# POWER_STAGE.net
KiCad netlist of a schematic drawn in Altium Designer
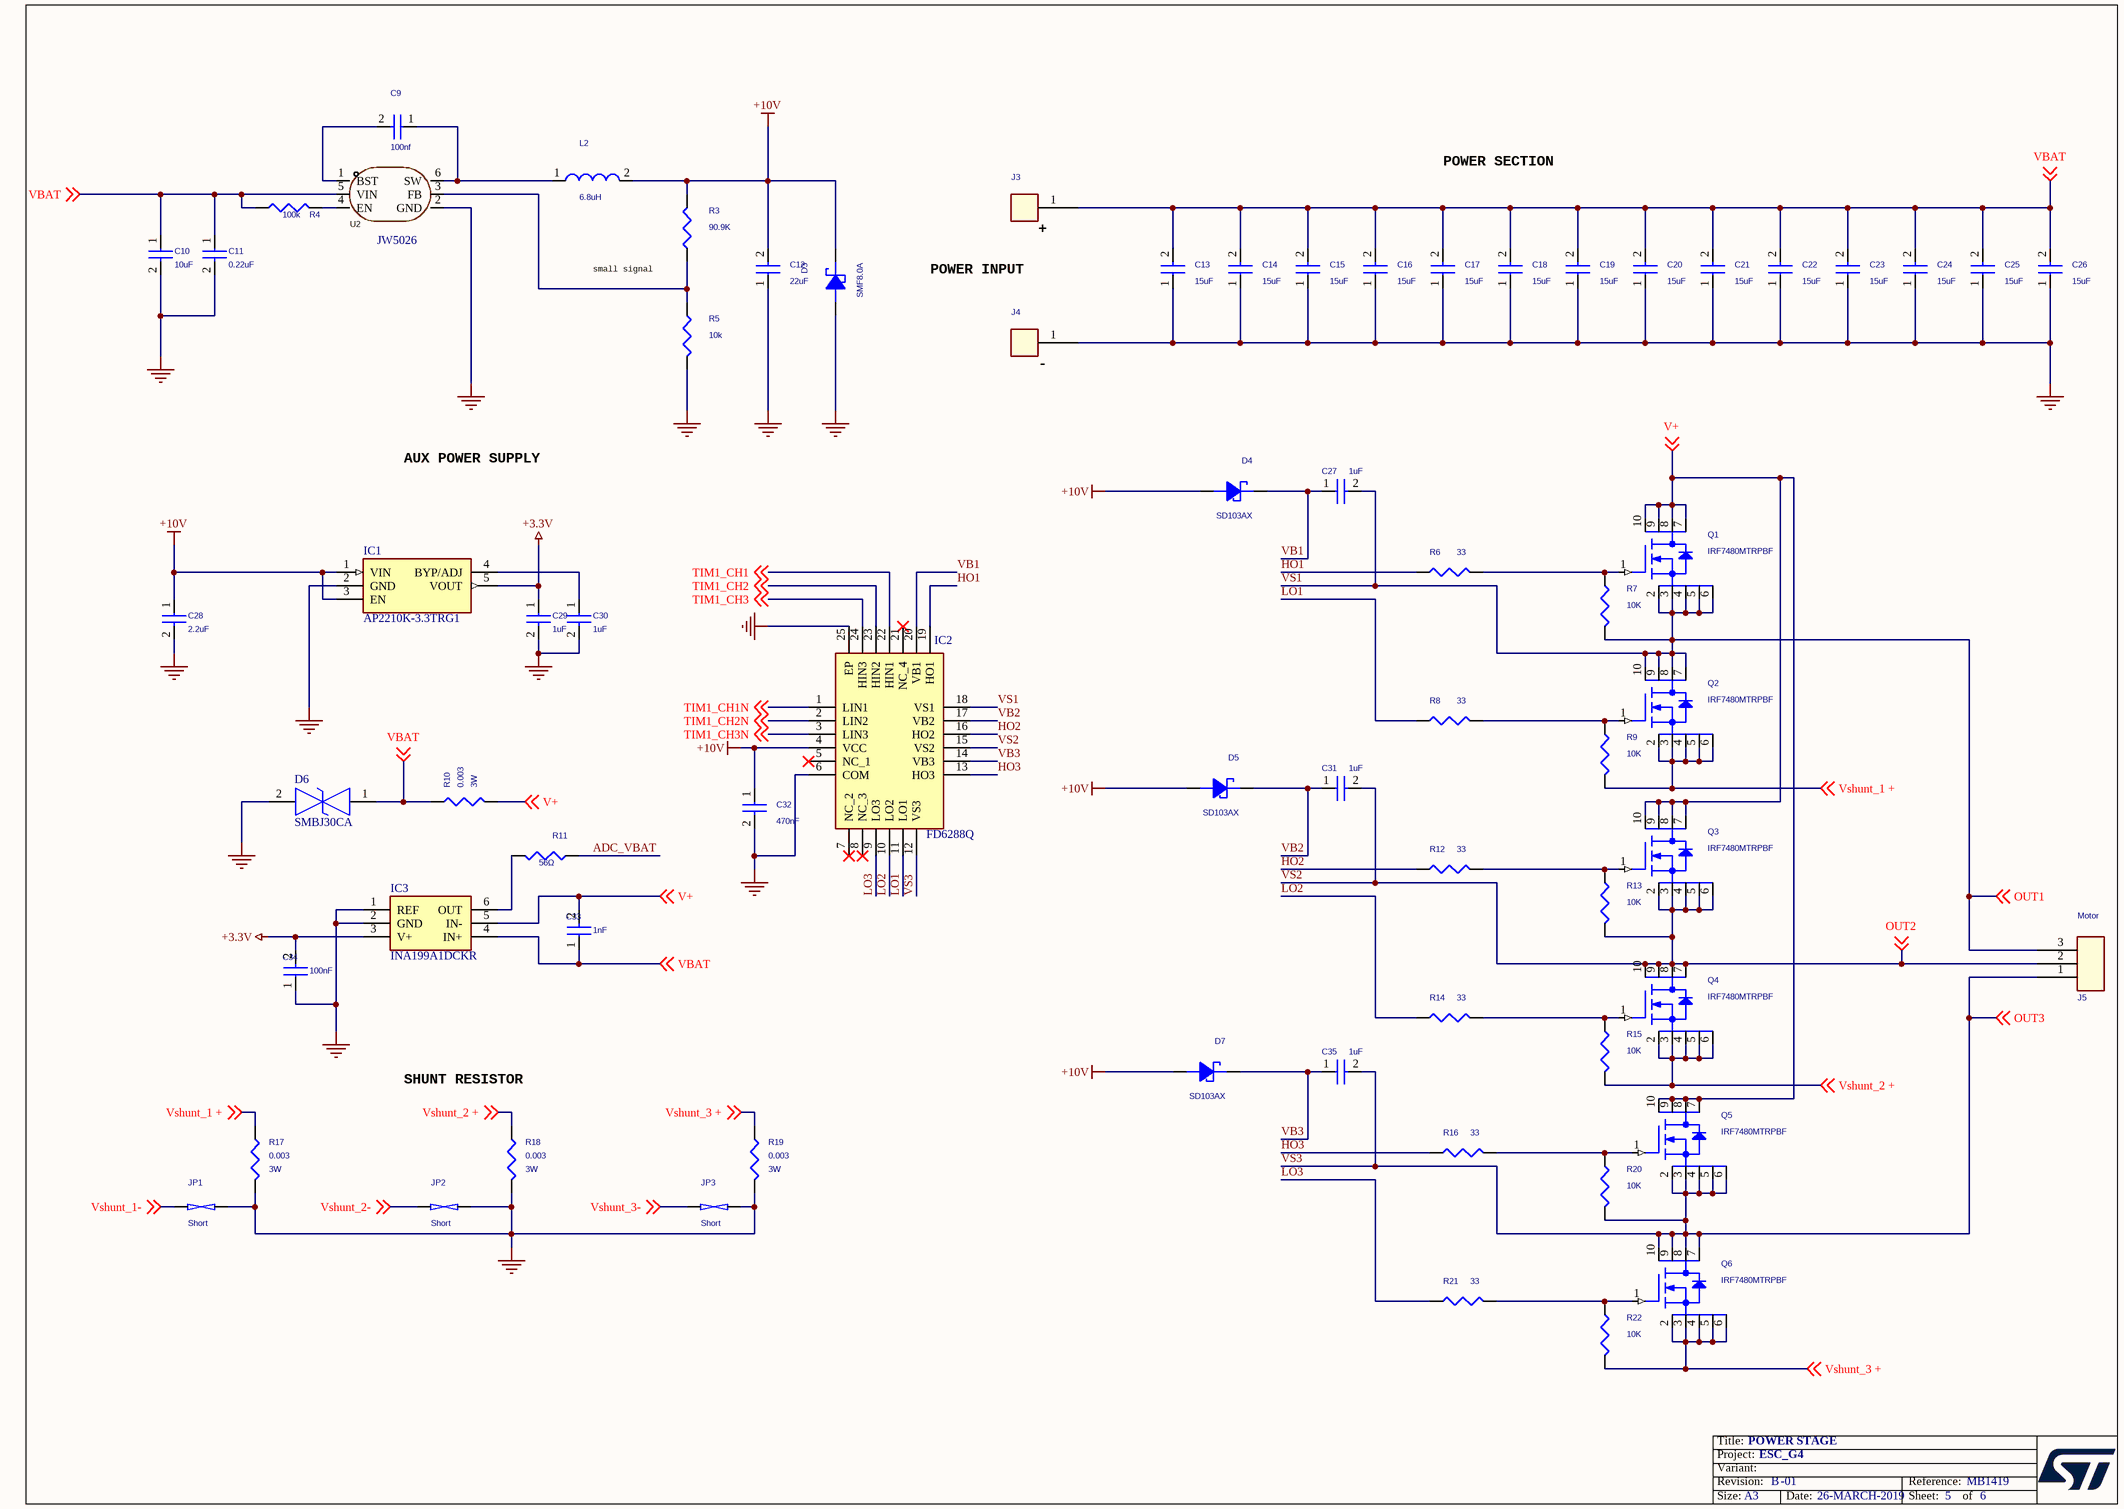
[diagram p0: POWER STAGE.SchDoc]

(export (version "E")
  (design (tool "Eeschema 10.0.6"))
  (components
    (comp (ref "C9")
      (value "100nf")
      (footprint "C_0402")
      (description "CAP CER 3900PF 16V X7R 0402")
      (fields (field (name "MANUFACTURER") "KEMET") (field (name "TOLERANCE") "10%"))
      (libsource (lib "*") (part "CAP_Dup1"))
    )
    (comp (ref "C10")
      (value "10uF")
      (footprint "C_1206")
      (description "CAP CER 10UF 50V X7R 1206")
      (fields
        (field (name "MANUFACTURER") "Samsung Electro-Mechanics America, Inc.")
        (field (name "TOLERANCE") "10%")
      )
      (libsource (lib "*") (part "CAP_Dup1"))
    )
    (comp (ref "C11")
      (value "0.22uF")
      (footprint "C_0603_HD")
      (description "CAP CER 0.22UF 50V X7R 0603")
      (fields (field (name "MANUFACTURER") "TDK Corporation") (field (name "TOLERANCE") "10%"))
      (libsource (lib "*") (part "CAP_Dup1"))
    )
    (comp (ref "C12")
      (value "22uF")
      (footprint "C_1206")
      (description "CAP CER 22UF 25V X5R 1206")
      (fields
        (field (name "MANUFACTURER") "Murata Electronics North America")
        (field (name "TOLERANCE") "20%")
      )
      (libsource (lib "*") (part "CAP_Dup1"))
    )
    (comp (ref "C13")
      (value "15uF")
      (footprint "C_0805_HD")
      (description "CAP CER 15UF 35V X5R 0805")
      (fields (field (name "PART_NUMBER") "TMP-773") (field (name "TOLERANCE") "20%"))
      (libsource (lib "*") (part "CAP_Dup1"))
    )
    (comp (ref "C14")
      (value "15uF")
      (footprint "C_0805_HD")
      (description "CAP CER 15UF 35V X5R 0805")
      (fields (field (name "PART_NUMBER") "TMP-773") (field (name "TOLERANCE") "20%"))
      (libsource (lib "*") (part "CAP_Dup1"))
    )
    (comp (ref "C15")
      (value "15uF")
      (footprint "C_0805_HD")
      (description "CAP CER 15UF 35V X5R 0805")
      (fields (field (name "PART_NUMBER") "TMP-773") (field (name "TOLERANCE") "20%"))
      (libsource (lib "*") (part "CAP_Dup1"))
    )
    (comp (ref "C16")
      (value "15uF")
      (footprint "C_0805_HD")
      (description "CAP CER 15UF 35V X5R 0805")
      (fields (field (name "PART_NUMBER") "TMP-773") (field (name "TOLERANCE") "20%"))
      (libsource (lib "*") (part "CAP_Dup1"))
    )
    (comp (ref "C17")
      (value "15uF")
      (footprint "C_0805_HD")
      (description "CAP CER 15UF 35V X5R 0805")
      (fields (field (name "PART_NUMBER") "TMP-773") (field (name "TOLERANCE") "20%"))
      (libsource (lib "*") (part "CAP_Dup1"))
    )
    (comp (ref "C18")
      (value "15uF")
      (footprint "C_0805_HD")
      (description "CAP CER 15UF 35V X5R 0805")
      (fields (field (name "PART_NUMBER") "TMP-773") (field (name "TOLERANCE") "20%"))
      (libsource (lib "*") (part "CAP_Dup1"))
    )
    (comp (ref "C19")
      (value "15uF")
      (footprint "C_0805_HD")
      (description "CAP CER 15UF 35V X5R 0805")
      (fields (field (name "PART_NUMBER") "TMP-773") (field (name "TOLERANCE") "20%"))
      (libsource (lib "*") (part "CAP_Dup1"))
    )
    (comp (ref "C20")
      (value "15uF")
      (footprint "C_0805_HD")
      (description "CAP CER 15UF 35V X5R 0805")
      (fields (field (name "PART_NUMBER") "TMP-773") (field (name "TOLERANCE") "20%"))
      (libsource (lib "*") (part "CAP_Dup1"))
    )
    (comp (ref "C21")
      (value "15uF")
      (footprint "C_0805_HD")
      (description "CAP CER 15UF 35V X5R 0805")
      (fields (field (name "PART_NUMBER") "TMP-773") (field (name "TOLERANCE") "20%"))
      (libsource (lib "*") (part "CAP_Dup1"))
    )
    (comp (ref "C22")
      (value "15uF")
      (footprint "C_0805_HD")
      (description "CAP CER 15UF 35V X5R 0805")
      (fields (field (name "PART_NUMBER") "TMP-773") (field (name "TOLERANCE") "20%"))
      (libsource (lib "*") (part "CAP_Dup1"))
    )
    (comp (ref "C23")
      (value "15uF")
      (footprint "C_0805_HD")
      (description "CAP CER 15UF 35V X5R 0805")
      (fields (field (name "PART_NUMBER") "TMP-773") (field (name "TOLERANCE") "20%"))
      (libsource (lib "*") (part "CAP_Dup1"))
    )
    (comp (ref "C24")
      (value "15uF")
      (footprint "C_0805_HD")
      (description "CAP CER 15UF 35V X5R 0805")
      (fields (field (name "PART_NUMBER") "TMP-773") (field (name "TOLERANCE") "20%"))
      (libsource (lib "*") (part "CAP_Dup1"))
    )
    (comp (ref "C25")
      (value "15uF")
      (footprint "C_0805_HD")
      (description "CAP CER 15UF 35V X5R 0805")
      (fields (field (name "PART_NUMBER") "TMP-773") (field (name "TOLERANCE") "20%"))
      (libsource (lib "*") (part "CAP_Dup1"))
    )
    (comp (ref "C26")
      (value "15uF")
      (footprint "C_0805_HD")
      (description "CAP CER 15UF 35V X5R 0805")
      (fields (field (name "PART_NUMBER") "TMP-773") (field (name "TOLERANCE") "20%"))
      (libsource (lib "*") (part "CAP_Dup1"))
    )
    (comp (ref "C27")
      (value "1uF")
      (footprint "C_0402")
      (description "CAP CER 10PF 10V C0G/NP0 0402")
      (fields (field (name "MANUFACTURER") "Wurth Electronics Inc.") (field (name "TOLERANCE") "5%"))
      (libsource (lib "MB1419") (part "CAP"))
    )
    (comp (ref "C28")
      (value "2.2uF")
      (footprint "C_0402")
      (description "CAP CER 2.2UF 10V X5R 0402")
      (fields (field (name "PART_NUMBER") "TMP-449") (field (name "TOLERANCE") "20%"))
      (libsource (lib "*") (part "CAP_Dup1"))
    )
    (comp (ref "C29")
      (value "1uF")
      (footprint "C_0402")
      (description "CAP CER 1UF 25V X5R 0402")
      (fields
        (field (name "MANUFACTURER") "Murata Electronics North America")
        (field (name "TOLERANCE") "10%")
      )
      (libsource (lib "*") (part "CAP_Dup1"))
    )
    (comp (ref "C30")
      (value "1uF")
      (footprint "C_0402")
      (description "CAP CER 1UF 25V X5R 0402")
      (fields
        (field (name "MANUFACTURER") "Murata Electronics North America")
        (field (name "TOLERANCE") "10%")
      )
      (libsource (lib "*") (part "CAP_Dup1"))
    )
    (comp (ref "C31")
      (value "1uF")
      (footprint "C_0402")
      (description "CAP CER 10PF 10V C0G/NP0 0402")
      (fields (field (name "MANUFACTURER") "Wurth Electronics Inc.") (field (name "TOLERANCE") "5%"))
      (libsource (lib "MB1419") (part "CAP"))
    )
    (comp (ref "C32")
      (value "470nF")
      (footprint "C_0603_HD")
      (description "CAP CER 0.47UF 25V X7R 0603")
      (fields (field (name "PART_NUMBER") "TMP-428") (field (name "TOLERANCE") "10%"))
      (libsource (lib "*") (part "CAP_Dup1"))
    )
    (comp (ref "C33")
      (value "1nF")
      (footprint "C_0402")
      (description "CAP CER 10PF 10V C0G/NP0 0402")
      (fields (field (name "MANUFACTURER") "Wurth Electronics Inc.") (field (name "TOLERANCE") "5%"))
      (libsource (lib "MB1419") (part "CAP"))
    )
    (comp (ref "C34")
      (value "100nF")
      (footprint "C_0402")
      (description "CAP CER 10PF 10V C0G/NP0 0402")
      (fields (field (name "MANUFACTURER") "Wurth Electronics Inc.") (field (name "TOLERANCE") "5%"))
      (libsource (lib "MB1419") (part "CAP"))
    )
    (comp (ref "C35")
      (value "1uF")
      (footprint "C_0402")
      (description "CAP CER 10PF 10V C0G/NP0 0402")
      (fields (field (name "MANUFACTURER") "Wurth Electronics Inc.") (field (name "TOLERANCE") "5%"))
      (libsource (lib "MB1419") (part "CAP"))
    )
    (comp (ref "D3")
      (value "SMF8.0A")
      (footprint "SODFL3618X108N")
      (description "DIODE SCHOTTKY 20V 1A STMITEFLAT")
      (fields (field (name "PART_NUMBER") "TMP-380") (field (name "MANUFACTURER") "STMicroelectronics"))
      (libsource (lib "MB1419") (part "DIODE_SCHOTTKY_0"))
    )
    (comp (ref "D4")
      (value "SD103AX")
      (footprint "SODFL1608X70N")
      (description "DIODE SCHOTTKY 20V 1A STMITEFLAT")
      (fields (field (name "MANUFACTURER") "STMicroelectronics") (field (name "PART_NUMBER") "TMP-380"))
      (libsource (lib "MB1419") (part "DIODE_SCHOTTKY_0"))
    )
    (comp (ref "D5")
      (value "SD103AX")
      (footprint "SODFL1608X70N")
      (description "DIODE SCHOTTKY 20V 1A STMITEFLAT")
      (fields (field (name "MANUFACTURER") "STMicroelectronics") (field (name "PART_NUMBER") "TMP-380"))
      (libsource (lib "MB1419") (part "DIODE_SCHOTTKY_0"))
    )
    (comp (ref "D6")
      (value "SMBJ30CA")
      (footprint "SMBJ50CA")
      (description "TVS Diode (Bi-directional)")
      (libsource (lib "MB1419") (part "SMBJ30CA"))
    )
    (comp (ref "D7")
      (value "SD103AX")
      (footprint "SODFL1608X70N")
      (description "DIODE SCHOTTKY 20V 1A STMITEFLAT")
      (fields (field (name "MANUFACTURER") "STMicroelectronics") (field (name "PART_NUMBER") "TMP-380"))
      (libsource (lib "MB1419") (part "DIODE_SCHOTTKY_0"))
    )
    (comp (ref "IC1")
      (value "AP2210K-3.3TRG1")
      (footprint "SOT95P280X145-5N")
      (description "Integrated Circuit")
      (fields (field (name "MOUSER PART NUMBER") "621-AP2210K-3.3TRG1"))
      (libsource (lib "MB1419") (part "AP2210K-3.3TRG1"))
    )
    (comp (ref "IC2")
      (value "FD6288Q")
      (footprint "QFN50P400X400X90-25N-D")
      (description "Integrated Circuit")
      (libsource (lib "MB1419") (part "FD6288Q"))
    )
    (comp (ref "IC3")
      (value "INA199A1DCKR")
      (footprint "SOT65P210X110-6N")
      (description "Integrated Circuit")
      (fields (field (name "MOUSER PART NUMBER") "595-INA199A1DCKR"))
      (libsource (lib "MB1419") (part "INA199A1DCKR"))
    )
    (comp (ref "J3")
      (value "CON1")
      (footprint "wire1_220s")
      (description "SOLDER PADS")
      (libsource (lib "*") (part "CON1"))
    )
    (comp (ref "J4")
      (value "CON1")
      (footprint "wire1_220s")
      (description "SOLDER PADS")
      (libsource (lib "*") (part "CON1"))
    )
    (comp (ref "J5")
      (value "Motor")
      (footprint "conn_motor_out")
      (description "SOLDER PADS")
      (libsource (lib "*") (part "CON3"))
    )
    (comp (ref "JP1")
      (value "Short")
      (footprint "SHORT")
      (description "2 PIN SHORTED TO CONNECT DIFFERENT NETS")
      (fields (field (name "PART_NUMBER") "TMP-442"))
      (libsource (lib "*") (part "SHORT"))
    )
    (comp (ref "JP2")
      (value "Short")
      (footprint "SHORT")
      (description "2 PIN SHORTED TO CONNECT DIFFERENT NETS")
      (fields (field (name "PART_NUMBER") "TMP-442"))
      (libsource (lib "*") (part "SHORT"))
    )
    (comp (ref "JP3")
      (value "Short")
      (footprint "SHORT")
      (description "2 PIN SHORTED TO CONNECT DIFFERENT NETS")
      (fields (field (name "PART_NUMBER") "TMP-442"))
      (libsource (lib "*") (part "SHORT"))
    )
    (comp (ref "L2")
      (value "6.8uH")
      (footprint "LQM2MPN1R0NG0L")
      (description "Fixed Inductors LPS4018 Low Profile 33uH 0.8A 20% SMD")
      (fields (field (name "MANUFACTURER") "Coilcraft") (field (name "TOLERANCE") "20%"))
      (libsource (lib "MB1419") (part "IND"))
    )
    (comp (ref "Q1")
      (value "IRF7480MTRPBF")
      (footprint "IRF7480MTRPBF")
      (description "N-channel 60 V, 1.9 mO typ., 120 A STripFET™ F7")
      (fields (field (name "PART_NUMBER") "TMP-772") (field (name "MANUFACTURER") "STMicroelectronics"))
      (libsource (lib "MB1419") (part "MOSFET_N"))
    )
    (comp (ref "Q2")
      (value "IRF7480MTRPBF")
      (footprint "IRF7480MTRPBF")
      (description "N-channel 60 V, 1.9 mO typ., 120 A STripFET™ F7")
      (fields (field (name "PART_NUMBER") "TMP-772") (field (name "MANUFACTURER") "STMicroelectronics"))
      (libsource (lib "MB1419") (part "MOSFET_N"))
    )
    (comp (ref "Q3")
      (value "IRF7480MTRPBF")
      (footprint "IRF7480MTRPBF")
      (description "N-channel 60 V, 1.9 mO typ., 120 A STripFET™ F7")
      (fields (field (name "PART_NUMBER") "TMP-772") (field (name "MANUFACTURER") "STMicroelectronics"))
      (libsource (lib "MB1419") (part "MOSFET_N"))
    )
    (comp (ref "Q4")
      (value "IRF7480MTRPBF")
      (footprint "IRF7480MTRPBF")
      (description "N-channel 60 V, 1.9 mO typ., 120 A STripFET™ F7")
      (fields (field (name "PART_NUMBER") "TMP-772") (field (name "MANUFACTURER") "STMicroelectronics"))
      (libsource (lib "MB1419") (part "MOSFET_N"))
    )
    (comp (ref "Q5")
      (value "IRF7480MTRPBF")
      (footprint "IRF7480MTRPBF")
      (description "N-channel 60 V, 1.9 mO typ., 120 A STripFET™ F7")
      (fields (field (name "PART_NUMBER") "TMP-772") (field (name "MANUFACTURER") "STMicroelectronics"))
      (libsource (lib "MB1419") (part "MOSFET_N"))
    )
    (comp (ref "Q6")
      (value "IRF7480MTRPBF")
      (footprint "IRF7480MTRPBF")
      (description "N-channel 60 V, 1.9 mO typ., 120 A STripFET™ F7")
      (fields (field (name "PART_NUMBER") "TMP-772") (field (name "MANUFACTURER") "STMicroelectronics"))
      (libsource (lib "MB1419") (part "MOSFET_N"))
    )
    (comp (ref "R3")
      (value "90.9K")
      (footprint "R_0402")
      (description "RES SMD 4.7K OHM 1% 1/16W 0402")
      (fields (field (name "MANUFACTURER") "TE Connectivity Passive Product") (field (name "TOLERANCE") "1%"))
      (libsource (lib "*") (part "RES"))
    )
    (comp (ref "R4")
      (value "100k")
      (footprint "R_0402")
      (description "RES SMD 34.8K OHM 1% 1/16W 0402")
      (fields (field (name "MANUFACTURER") "Yageo") (field (name "TOLERANCE") "1%"))
      (libsource (lib "*") (part "RES"))
    )
    (comp (ref "R5")
      (value "10k")
      (footprint "R_0402")
      (description "RES SMD 300 OHM 1% 1/16W 0402")
      (fields (field (name "PART_NUMBER") "TMP-418") (field (name "TOLERANCE") "1%"))
      (libsource (lib "*") (part "RES"))
    )
    (comp (ref "R6")
      (value "33")
      (footprint "R_0402")
      (description "RES SMD 33 OHM 1% 1/16W 0402")
      (fields (field (name "PART_NUMBER") "TMP-441") (field (name "TOLERANCE") "1%"))
      (libsource (lib "MB1419") (part "RES"))
    )
    (comp (ref "R7")
      (value "10K")
      (footprint "R_0402")
      (description "RES SMD 10K OHM 1% 1/16W 0402")
      (fields (field (name "MANUFACTURER") "Yageo") (field (name "TOLERANCE") "1%"))
      (libsource (lib "*") (part "RES"))
    )
    (comp (ref "R8")
      (value "33")
      (footprint "R_0402")
      (description "RES SMD 33 OHM 1% 1/16W 0402")
      (fields (field (name "PART_NUMBER") "TMP-441") (field (name "TOLERANCE") "1%"))
      (libsource (lib "MB1419") (part "RES"))
    )
    (comp (ref "R9")
      (value "10K")
      (footprint "R_0402")
      (description "RES SMD 10K OHM 1% 1/16W 0402")
      (fields (field (name "MANUFACTURER") "Yageo") (field (name "TOLERANCE") "1%"))
      (libsource (lib "*") (part "RES"))
    )
    (comp (ref "R10")
      (value "0.003")
      (footprint "resc635x300x60l193n")
      (description "RES 0.003 OHM 1% 3W 2512")
      (fields
        (field (name "MANUFACTURER") "TE Connectivity Passive Product")
        (field (name "RATED POWER") "3W")
        (field (name "TOLERANCE") "1%")
      )
      (libsource (lib "*") (part "RES"))
    )
    (comp (ref "R11")
      (value "56Ω")
      (footprint "R_0402")
      (description "RES SMD 30.9K OHM 1% 1/10W 0402")
      (fields (field (name "PART_NUMBER") "TMP-448") (field (name "TOLERANCE") "1%"))
      (libsource (lib "*") (part "RES"))
    )
    (comp (ref "R12")
      (value "33")
      (footprint "R_0402")
      (description "RES SMD 33 OHM 1% 1/16W 0402")
      (fields (field (name "PART_NUMBER") "TMP-441") (field (name "TOLERANCE") "1%"))
      (libsource (lib "MB1419") (part "RES"))
    )
    (comp (ref "R13")
      (value "10K")
      (footprint "R_0402")
      (description "RES SMD 10K OHM 1% 1/16W 0402")
      (fields (field (name "MANUFACTURER") "Yageo") (field (name "TOLERANCE") "1%"))
      (libsource (lib "*") (part "RES"))
    )
    (comp (ref "R14")
      (value "33")
      (footprint "R_0402")
      (description "RES SMD 33 OHM 1% 1/16W 0402")
      (fields (field (name "PART_NUMBER") "TMP-441") (field (name "TOLERANCE") "1%"))
      (libsource (lib "MB1419") (part "RES"))
    )
    (comp (ref "R15")
      (value "10K")
      (footprint "R_0402")
      (description "RES SMD 10K OHM 1% 1/16W 0402")
      (fields (field (name "MANUFACTURER") "Yageo") (field (name "TOLERANCE") "1%"))
      (libsource (lib "*") (part "RES"))
    )
    (comp (ref "R16")
      (value "33")
      (footprint "R_0402")
      (description "RES SMD 33 OHM 1% 1/16W 0402")
      (fields (field (name "PART_NUMBER") "TMP-441") (field (name "TOLERANCE") "1%"))
      (libsource (lib "MB1419") (part "RES"))
    )
    (comp (ref "R17")
      (value "0.003")
      (footprint "resc635x300x60l193n")
      (description "RES 0.003 OHM 1% 3W 2512")
      (fields
        (field (name "PART_NUMBER") "TMP-766")
        (field (name "TOLERANCE") "1%")
        (field (name "RATED POWER") "3W")
      )
      (libsource (lib "*") (part "RES"))
    )
    (comp (ref "R18")
      (value "0.003")
      (footprint "resc635x300x60l193n")
      (description "RES 0.003 OHM 1% 3W 2512")
      (fields
        (field (name "MANUFACTURER") "TE Connectivity Passive Product")
        (field (name "RATED POWER") "3W")
        (field (name "TOLERANCE") "1%")
      )
      (libsource (lib "*") (part "RES"))
    )
    (comp (ref "R19")
      (value "0.003")
      (footprint "resc635x300x60l193n")
      (description "RES 0.003 OHM 1% 3W 2512")
      (fields
        (field (name "PART_NUMBER") "TMP-766")
        (field (name "TOLERANCE") "1%")
        (field (name "RATED POWER") "3W")
      )
      (libsource (lib "*") (part "RES"))
    )
    (comp (ref "R20")
      (value "10K")
      (footprint "R_0402")
      (description "RES SMD 10K OHM 1% 1/16W 0402")
      (fields (field (name "PART_NUMBER") "TMP-396") (field (name "TOLERANCE") "1%"))
      (libsource (lib "*") (part "RES"))
    )
    (comp (ref "R21")
      (value "33")
      (footprint "R_0402")
      (description "RES SMD 33 OHM 1% 1/16W 0402")
      (fields (field (name "PART_NUMBER") "TMP-441") (field (name "TOLERANCE") "1%"))
      (libsource (lib "MB1419") (part "RES"))
    )
    (comp (ref "R22")
      (value "10K")
      (footprint "R_0402")
      (description "RES SMD 10K OHM 1% 1/16W 0402")
      (fields (field (name "PART_NUMBER") "TMP-396") (field (name "TOLERANCE") "1%"))
      (libsource (lib "*") (part "RES"))
    )
    (comp (ref "U2")
      (value "JW5026")
      (footprint "SOT-23-6_L2.9-W1.6-P0.95-LS2.8-BR")
      (fields (field (name "MANUFACTURER") "Joulwatt(杰华特)"))
      (libsource (lib "MB1419") (part "JW5026"))
    )
  )
  (nets
    (net (code "1") (name "+3.3V") (class "Default")
      (node (ref "C29") (pin "1") (pinfunction "1_1") (pintype "passive"))
      (node (ref "C34") (pin "2") (pinfunction "2_2") (pintype "passive"))
      (node (ref "IC1") (pin "5") (pinfunction "VOUT_5") (pintype "output"))
      (node (ref "IC3") (pin "3") (pinfunction "V+_3") (pintype "passive"))
    )
    (net (code "2") (name "+10V") (class "Default")
      (node (ref "C12") (pin "2") (pinfunction "2_2") (pintype "passive"))
      (node (ref "C28") (pin "1") (pinfunction "1_1") (pintype "passive"))
      (node (ref "C32") (pin "1") (pinfunction "1_1") (pintype "passive"))
      (node (ref "D3") (pin "C") (pinfunction "C_C") (pintype "passive"))
      (node (ref "D4") (pin "A") (pinfunction "A_A") (pintype "passive"))
      (node (ref "D5") (pin "A") (pinfunction "A_A") (pintype "passive"))
      (node (ref "D7") (pin "A") (pinfunction "A_A") (pintype "passive"))
      (node (ref "IC1") (pin "1") (pinfunction "VIN_1") (pintype "input"))
      (node (ref "IC1") (pin "3") (pinfunction "EN_3") (pintype "passive"))
      (node (ref "IC2") (pin "4") (pinfunction "VCC_4") (pintype "passive"))
      (node (ref "L2") (pin "2") (pinfunction "2_2") (pintype "passive"))
      (node (ref "R3") (pin "1") (pinfunction "1_1") (pintype "passive"))
    )
    (net (code "3") (name "/ADC_VBAT") (class "Default")
      (node (ref "R11") (pin "1") (pinfunction "1_1") (pintype "passive"))
    )
    (net (code "4") (name "/HO1") (class "Default")
      (node (ref "IC2") (pin "19") (pinfunction "HO1_19") (pintype "passive"))
      (node (ref "R6") (pin "1") (pinfunction "1_1") (pintype "passive"))
    )
    (net (code "5") (name "/HO2") (class "Default")
      (node (ref "IC2") (pin "16") (pinfunction "HO2_16") (pintype "passive"))
      (node (ref "R12") (pin "1") (pinfunction "1_1") (pintype "passive"))
    )
    (net (code "6") (name "/HO3") (class "Default")
      (node (ref "IC2") (pin "13") (pinfunction "HO3_13") (pintype "passive"))
      (node (ref "R16") (pin "1") (pinfunction "1_1") (pintype "passive"))
    )
    (net (code "7") (name "/LO1") (class "Default")
      (node (ref "IC2") (pin "11") (pinfunction "LO1_11") (pintype "passive"))
      (node (ref "R8") (pin "1") (pinfunction "1_1") (pintype "passive"))
    )
    (net (code "8") (name "/LO2") (class "Default")
      (node (ref "IC2") (pin "10") (pinfunction "LO2_10") (pintype "passive"))
      (node (ref "R14") (pin "1") (pinfunction "1_1") (pintype "passive"))
    )
    (net (code "9") (name "/LO3") (class "Default")
      (node (ref "IC2") (pin "9") (pinfunction "LO3_9") (pintype "passive"))
      (node (ref "R21") (pin "1") (pinfunction "1_1") (pintype "passive"))
    )
    (net (code "10") (name "/VB1") (class "Default")
      (node (ref "C27") (pin "1") (pinfunction "1_1") (pintype "passive"))
      (node (ref "D4") (pin "C") (pinfunction "C_C") (pintype "passive"))
      (node (ref "IC2") (pin "20") (pinfunction "VB1_20") (pintype "passive"))
    )
    (net (code "11") (name "/VB2") (class "Default")
      (node (ref "C31") (pin "1") (pinfunction "1_1") (pintype "passive"))
      (node (ref "D5") (pin "C") (pinfunction "C_C") (pintype "passive"))
      (node (ref "IC2") (pin "17") (pinfunction "VB2_17") (pintype "passive"))
    )
    (net (code "12") (name "/VB3") (class "Default")
      (node (ref "C35") (pin "1") (pinfunction "1_1") (pintype "passive"))
      (node (ref "D7") (pin "C") (pinfunction "C_C") (pintype "passive"))
      (node (ref "IC2") (pin "14") (pinfunction "VB3_14") (pintype "passive"))
    )
    (net (code "13") (name "GND") (class "Default")
      (node (ref "C10") (pin "2") (pinfunction "2_2") (pintype "passive"))
      (node (ref "C11") (pin "2") (pinfunction "2_2") (pintype "passive"))
      (node (ref "C12") (pin "1") (pinfunction "1_1") (pintype "passive"))
      (node (ref "C13") (pin "1") (pinfunction "1_1") (pintype "passive"))
      (node (ref "C14") (pin "1") (pinfunction "1_1") (pintype "passive"))
      (node (ref "C15") (pin "1") (pinfunction "1_1") (pintype "passive"))
      (node (ref "C16") (pin "1") (pinfunction "1_1") (pintype "passive"))
      (node (ref "C17") (pin "1") (pinfunction "1_1") (pintype "passive"))
      (node (ref "C18") (pin "1") (pinfunction "1_1") (pintype "passive"))
      (node (ref "C19") (pin "1") (pinfunction "1_1") (pintype "passive"))
      (node (ref "C20") (pin "1") (pinfunction "1_1") (pintype "passive"))
      (node (ref "C21") (pin "1") (pinfunction "1_1") (pintype "passive"))
      (node (ref "C22") (pin "1") (pinfunction "1_1") (pintype "passive"))
      (node (ref "C23") (pin "1") (pinfunction "1_1") (pintype "passive"))
      (node (ref "C24") (pin "1") (pinfunction "1_1") (pintype "passive"))
      (node (ref "C25") (pin "1") (pinfunction "1_1") (pintype "passive"))
      (node (ref "C26") (pin "1") (pinfunction "1_1") (pintype "passive"))
      (node (ref "C28") (pin "2") (pinfunction "2_2") (pintype "passive"))
      (node (ref "C29") (pin "2") (pinfunction "2_2") (pintype "passive"))
      (node (ref "C30") (pin "2") (pinfunction "2_2") (pintype "passive"))
      (node (ref "C32") (pin "2") (pinfunction "2_2") (pintype "passive"))
      (node (ref "C34") (pin "1") (pinfunction "1_1") (pintype "passive"))
      (node (ref "D3") (pin "A") (pinfunction "A_A") (pintype "passive"))
      (node (ref "D6") (pin "2") (pinfunction "2_2") (pintype "passive"))
      (node (ref "IC1") (pin "2") (pinfunction "GND_2") (pintype "power_in"))
      (node (ref "IC2") (pin "25") (pinfunction "EP_25") (pintype "passive"))
      (node (ref "IC2") (pin "6") (pinfunction "COM_6") (pintype "passive"))
      (node (ref "IC3") (pin "1") (pinfunction "REF_1") (pintype "passive"))
      (node (ref "IC3") (pin "2") (pinfunction "GND_2") (pintype "passive"))
      (node (ref "J4") (pin "1") (pinfunction "1_1") (pintype "passive"))
      (node (ref "JP1") (pin "2") (pinfunction "2_2") (pintype "passive"))
      (node (ref "JP2") (pin "2") (pinfunction "2_2") (pintype "passive"))
      (node (ref "JP3") (pin "2") (pinfunction "2_2") (pintype "passive"))
      (node (ref "R17") (pin "2") (pinfunction "2_2") (pintype "passive"))
      (node (ref "R18") (pin "2") (pinfunction "2_2") (pintype "passive"))
      (node (ref "R19") (pin "2") (pinfunction "2_2") (pintype "passive"))
      (node (ref "R5") (pin "1") (pinfunction "1_1") (pintype "passive"))
      (node (ref "U2") (pin "2") (pinfunction "GND_2") (pintype "passive"))
    )
    (net (code "14") (name "Net-(IC1-BYP{slash}ADJ)") (class "Default")
      (node (ref "C30") (pin "1") (pinfunction "1_1") (pintype "passive"))
      (node (ref "IC1") (pin "4") (pinfunction "BYP/ADJ_4") (pintype "passive"))
    )
    (net (code "15") (name "Net-(IC3-OUT)") (class "Default")
      (node (ref "IC3") (pin "6") (pinfunction "OUT_6") (pintype "passive"))
      (node (ref "R11") (pin "2") (pinfunction "2_2") (pintype "passive"))
    )
    (net (code "16") (name "Net-(Q1-G)") (class "Default")
      (node (ref "Q1") (pin "1") (pinfunction "G_1") (pintype "input"))
      (node (ref "R6") (pin "2") (pinfunction "2_2") (pintype "passive"))
      (node (ref "R7") (pin "1") (pinfunction "1_1") (pintype "passive"))
    )
    (net (code "17") (name "Net-(Q2-G)") (class "Default")
      (node (ref "Q2") (pin "1") (pinfunction "G_1") (pintype "input"))
      (node (ref "R8") (pin "2") (pinfunction "2_2") (pintype "passive"))
      (node (ref "R9") (pin "1") (pinfunction "1_1") (pintype "passive"))
    )
    (net (code "18") (name "Net-(Q3-G)") (class "Default")
      (node (ref "Q3") (pin "1") (pinfunction "G_1") (pintype "input"))
      (node (ref "R12") (pin "2") (pinfunction "2_2") (pintype "passive"))
      (node (ref "R13") (pin "1") (pinfunction "1_1") (pintype "passive"))
    )
    (net (code "19") (name "Net-(Q4-G)") (class "Default")
      (node (ref "Q4") (pin "1") (pinfunction "G_1") (pintype "input"))
      (node (ref "R14") (pin "2") (pinfunction "2_2") (pintype "passive"))
      (node (ref "R15") (pin "1") (pinfunction "1_1") (pintype "passive"))
    )
    (net (code "20") (name "Net-(Q5-G)") (class "Default")
      (node (ref "Q5") (pin "1") (pinfunction "G_1") (pintype "input"))
      (node (ref "R16") (pin "2") (pinfunction "2_2") (pintype "passive"))
      (node (ref "R20") (pin "1") (pinfunction "1_1") (pintype "passive"))
    )
    (net (code "21") (name "Net-(Q6-G)") (class "Default")
      (node (ref "Q6") (pin "1") (pinfunction "G_1") (pintype "input"))
      (node (ref "R21") (pin "2") (pinfunction "2_2") (pintype "passive"))
      (node (ref "R22") (pin "1") (pinfunction "1_1") (pintype "passive"))
    )
    (net (code "22") (name "Net-(U2-BST)") (class "Default")
      (node (ref "C9") (pin "2") (pinfunction "2_2") (pintype "passive"))
      (node (ref "U2") (pin "1") (pinfunction "BST_1") (pintype "passive"))
    )
    (net (code "23") (name "Net-(U2-EN)") (class "Default")
      (node (ref "R4") (pin "1") (pinfunction "1_1") (pintype "passive"))
      (node (ref "U2") (pin "4") (pinfunction "EN_4") (pintype "passive"))
    )
    (net (code "24") (name "Net-(U2-FB)") (class "Default")
      (node (ref "R3") (pin "2") (pinfunction "2_2") (pintype "passive"))
      (node (ref "R5") (pin "2") (pinfunction "2_2") (pintype "passive"))
      (node (ref "U2") (pin "3") (pinfunction "FB_3") (pintype "passive"))
    )
    (net (code "25") (name "Net-(U2-SW)") (class "Default")
      (node (ref "C9") (pin "1") (pinfunction "1_1") (pintype "passive"))
      (node (ref "L2") (pin "1") (pinfunction "1_1") (pintype "passive"))
      (node (ref "U2") (pin "6") (pinfunction "SW_6") (pintype "passive"))
    )
    (net (code "26") (name "OUT1") (class "Default")
      (node (ref "C27") (pin "2") (pinfunction "2_2") (pintype "passive"))
      (node (ref "IC2") (pin "18") (pinfunction "VS1_18") (pintype "passive"))
      (node (ref "J5") (pin "3") (pinfunction "3_3") (pintype "passive"))
      (node (ref "Q1") (pin "2") (pinfunction "S1_2") (pintype "passive"))
      (node (ref "Q1") (pin "3") (pinfunction "S2_3") (pintype "passive"))
      (node (ref "Q1") (pin "4") (pinfunction "S3_4") (pintype "passive"))
      (node (ref "Q1") (pin "5") (pinfunction "S4_5") (pintype "passive"))
      (node (ref "Q1") (pin "6") (pinfunction "S5_6") (pintype "passive"))
      (node (ref "Q2") (pin "10") (pinfunction "D10_10") (pintype "passive"))
      (node (ref "Q2") (pin "7") (pinfunction "D7_7") (pintype "passive"))
      (node (ref "Q2") (pin "8") (pinfunction "D8_8") (pintype "passive"))
      (node (ref "Q2") (pin "9") (pinfunction "D9_9") (pintype "passive"))
      (node (ref "R7") (pin "2") (pinfunction "2_2") (pintype "passive"))
    )
    (net (code "27") (name "OUT2") (class "Default")
      (node (ref "C31") (pin "2") (pinfunction "2_2") (pintype "passive"))
      (node (ref "IC2") (pin "15") (pinfunction "VS2_15") (pintype "passive"))
      (node (ref "J5") (pin "2") (pinfunction "2_2") (pintype "passive"))
      (node (ref "Q3") (pin "2") (pinfunction "S1_2") (pintype "passive"))
      (node (ref "Q3") (pin "3") (pinfunction "S2_3") (pintype "passive"))
      (node (ref "Q3") (pin "4") (pinfunction "S3_4") (pintype "passive"))
      (node (ref "Q3") (pin "5") (pinfunction "S4_5") (pintype "passive"))
      (node (ref "Q3") (pin "6") (pinfunction "S5_6") (pintype "passive"))
      (node (ref "Q4") (pin "10") (pinfunction "D10_10") (pintype "passive"))
      (node (ref "Q4") (pin "7") (pinfunction "D7_7") (pintype "passive"))
      (node (ref "Q4") (pin "8") (pinfunction "D8_8") (pintype "passive"))
      (node (ref "Q4") (pin "9") (pinfunction "D9_9") (pintype "passive"))
      (node (ref "R13") (pin "2") (pinfunction "2_2") (pintype "passive"))
    )
    (net (code "28") (name "OUT3") (class "Default")
      (node (ref "C35") (pin "2") (pinfunction "2_2") (pintype "passive"))
      (node (ref "IC2") (pin "12") (pinfunction "VS3_12") (pintype "passive"))
      (node (ref "J5") (pin "1") (pinfunction "1_1") (pintype "passive"))
      (node (ref "Q5") (pin "2") (pinfunction "S1_2") (pintype "passive"))
      (node (ref "Q5") (pin "3") (pinfunction "S2_3") (pintype "passive"))
      (node (ref "Q5") (pin "4") (pinfunction "S3_4") (pintype "passive"))
      (node (ref "Q5") (pin "5") (pinfunction "S4_5") (pintype "passive"))
      (node (ref "Q5") (pin "6") (pinfunction "S5_6") (pintype "passive"))
      (node (ref "Q6") (pin "10") (pinfunction "D10_10") (pintype "passive"))
      (node (ref "Q6") (pin "7") (pinfunction "D7_7") (pintype "passive"))
      (node (ref "Q6") (pin "8") (pinfunction "D8_8") (pintype "passive"))
      (node (ref "Q6") (pin "9") (pinfunction "D9_9") (pintype "passive"))
      (node (ref "R20") (pin "2") (pinfunction "2_2") (pintype "passive"))
    )
    (net (code "29") (name "TIM1_CH1") (class "Default")
      (node (ref "IC2") (pin "22") (pinfunction "HIN1_22") (pintype "passive"))
    )
    (net (code "30") (name "TIM1_CH1N") (class "Default")
      (node (ref "IC2") (pin "1") (pinfunction "LIN1_1") (pintype "passive"))
    )
    (net (code "31") (name "TIM1_CH2") (class "Default")
      (node (ref "IC2") (pin "23") (pinfunction "HIN2_23") (pintype "passive"))
    )
    (net (code "32") (name "TIM1_CH2N") (class "Default")
      (node (ref "IC2") (pin "2") (pinfunction "LIN2_2") (pintype "passive"))
    )
    (net (code "33") (name "TIM1_CH3") (class "Default")
      (node (ref "IC2") (pin "24") (pinfunction "HIN3_24") (pintype "passive"))
    )
    (net (code "34") (name "TIM1_CH3N") (class "Default")
      (node (ref "IC2") (pin "3") (pinfunction "LIN3_3") (pintype "passive"))
    )
    (net (code "35") (name "V+") (class "Default")
      (node (ref "C33") (pin "2") (pinfunction "2_2") (pintype "passive"))
      (node (ref "IC3") (pin "5") (pinfunction "IN-_5") (pintype "passive"))
      (node (ref "Q1") (pin "10") (pinfunction "D10_10") (pintype "passive"))
      (node (ref "Q1") (pin "7") (pinfunction "D7_7") (pintype "passive"))
      (node (ref "Q1") (pin "8") (pinfunction "D8_8") (pintype "passive"))
      (node (ref "Q1") (pin "9") (pinfunction "D9_9") (pintype "passive"))
      (node (ref "Q3") (pin "10") (pinfunction "D10_10") (pintype "passive"))
      (node (ref "Q3") (pin "7") (pinfunction "D7_7") (pintype "passive"))
      (node (ref "Q3") (pin "8") (pinfunction "D8_8") (pintype "passive"))
      (node (ref "Q3") (pin "9") (pinfunction "D9_9") (pintype "passive"))
      (node (ref "Q5") (pin "10") (pinfunction "D10_10") (pintype "passive"))
      (node (ref "Q5") (pin "7") (pinfunction "D7_7") (pintype "passive"))
      (node (ref "Q5") (pin "8") (pinfunction "D8_8") (pintype "passive"))
      (node (ref "Q5") (pin "9") (pinfunction "D9_9") (pintype "passive"))
      (node (ref "R10") (pin "2") (pinfunction "2_2") (pintype "passive"))
    )
    (net (code "36") (name "VBAT") (class "Default")
      (node (ref "C10") (pin "1") (pinfunction "1_1") (pintype "passive"))
      (node (ref "C11") (pin "1") (pinfunction "1_1") (pintype "passive"))
      (node (ref "C13") (pin "2") (pinfunction "2_2") (pintype "passive"))
      (node (ref "C14") (pin "2") (pinfunction "2_2") (pintype "passive"))
      (node (ref "C15") (pin "2") (pinfunction "2_2") (pintype "passive"))
      (node (ref "C16") (pin "2") (pinfunction "2_2") (pintype "passive"))
      (node (ref "C17") (pin "2") (pinfunction "2_2") (pintype "passive"))
      (node (ref "C18") (pin "2") (pinfunction "2_2") (pintype "passive"))
      (node (ref "C19") (pin "2") (pinfunction "2_2") (pintype "passive"))
      (node (ref "C20") (pin "2") (pinfunction "2_2") (pintype "passive"))
      (node (ref "C21") (pin "2") (pinfunction "2_2") (pintype "passive"))
      (node (ref "C22") (pin "2") (pinfunction "2_2") (pintype "passive"))
      (node (ref "C23") (pin "2") (pinfunction "2_2") (pintype "passive"))
      (node (ref "C24") (pin "2") (pinfunction "2_2") (pintype "passive"))
      (node (ref "C25") (pin "2") (pinfunction "2_2") (pintype "passive"))
      (node (ref "C26") (pin "2") (pinfunction "2_2") (pintype "passive"))
      (node (ref "C33") (pin "1") (pinfunction "1_1") (pintype "passive"))
      (node (ref "D6") (pin "1") (pinfunction "1_1") (pintype "passive"))
      (node (ref "IC3") (pin "4") (pinfunction "IN+_4") (pintype "passive"))
      (node (ref "J3") (pin "1") (pinfunction "1_1") (pintype "passive"))
      (node (ref "R10") (pin "1") (pinfunction "1_1") (pintype "passive"))
      (node (ref "R4") (pin "2") (pinfunction "2_2") (pintype "passive"))
      (node (ref "U2") (pin "5") (pinfunction "VIN_5") (pintype "passive"))
    )
    (net (code "37") (name "Vshunt_1 +") (class "Default")
      (node (ref "Q2") (pin "2") (pinfunction "S1_2") (pintype "passive"))
      (node (ref "Q2") (pin "3") (pinfunction "S2_3") (pintype "passive"))
      (node (ref "Q2") (pin "4") (pinfunction "S3_4") (pintype "passive"))
      (node (ref "Q2") (pin "5") (pinfunction "S4_5") (pintype "passive"))
      (node (ref "Q2") (pin "6") (pinfunction "S5_6") (pintype "passive"))
      (node (ref "R17") (pin "1") (pinfunction "1_1") (pintype "passive"))
      (node (ref "R9") (pin "2") (pinfunction "2_2") (pintype "passive"))
    )
    (net (code "38") (name "Vshunt_1-") (class "Default")
      (node (ref "JP1") (pin "1") (pinfunction "1_1") (pintype "passive"))
    )
    (net (code "39") (name "Vshunt_2 +") (class "Default")
      (node (ref "Q4") (pin "2") (pinfunction "S1_2") (pintype "passive"))
      (node (ref "Q4") (pin "3") (pinfunction "S2_3") (pintype "passive"))
      (node (ref "Q4") (pin "4") (pinfunction "S3_4") (pintype "passive"))
      (node (ref "Q4") (pin "5") (pinfunction "S4_5") (pintype "passive"))
      (node (ref "Q4") (pin "6") (pinfunction "S5_6") (pintype "passive"))
      (node (ref "R15") (pin "2") (pinfunction "2_2") (pintype "passive"))
      (node (ref "R18") (pin "1") (pinfunction "1_1") (pintype "passive"))
    )
    (net (code "40") (name "Vshunt_2-") (class "Default")
      (node (ref "JP2") (pin "1") (pinfunction "1_1") (pintype "passive"))
    )
    (net (code "41") (name "Vshunt_3 +") (class "Default")
      (node (ref "Q6") (pin "2") (pinfunction "S1_2") (pintype "passive"))
      (node (ref "Q6") (pin "3") (pinfunction "S2_3") (pintype "passive"))
      (node (ref "Q6") (pin "4") (pinfunction "S3_4") (pintype "passive"))
      (node (ref "Q6") (pin "5") (pinfunction "S4_5") (pintype "passive"))
      (node (ref "Q6") (pin "6") (pinfunction "S5_6") (pintype "passive"))
      (node (ref "R19") (pin "1") (pinfunction "1_1") (pintype "passive"))
      (node (ref "R22") (pin "2") (pinfunction "2_2") (pintype "passive"))
    )
    (net (code "42") (name "Vshunt_3-") (class "Default")
      (node (ref "JP3") (pin "1") (pinfunction "1_1") (pintype "passive"))
    )
    (net (code "43") (name "unconnected-(IC2-NC_1-Pad5)") (class "Default")
      (node (ref "IC2") (pin "5") (pinfunction "NC_1_5") (pintype "passive+no_connect"))
    )
    (net (code "44") (name "unconnected-(IC2-NC_2-Pad7)") (class "Default")
      (node (ref "IC2") (pin "7") (pinfunction "NC_2_7") (pintype "passive+no_connect"))
    )
    (net (code "45") (name "unconnected-(IC2-NC_3-Pad8)") (class "Default")
      (node (ref "IC2") (pin "8") (pinfunction "NC_3_8") (pintype "passive+no_connect"))
    )
    (net (code "46") (name "unconnected-(IC2-NC_4-Pad21)") (class "Default")
      (node (ref "IC2") (pin "21") (pinfunction "NC_4_21") (pintype "passive+no_connect"))
    )
  )
)
